# Holder_PCB_v1.net
KiCad netlist of a schematic drawn in Altium Designer
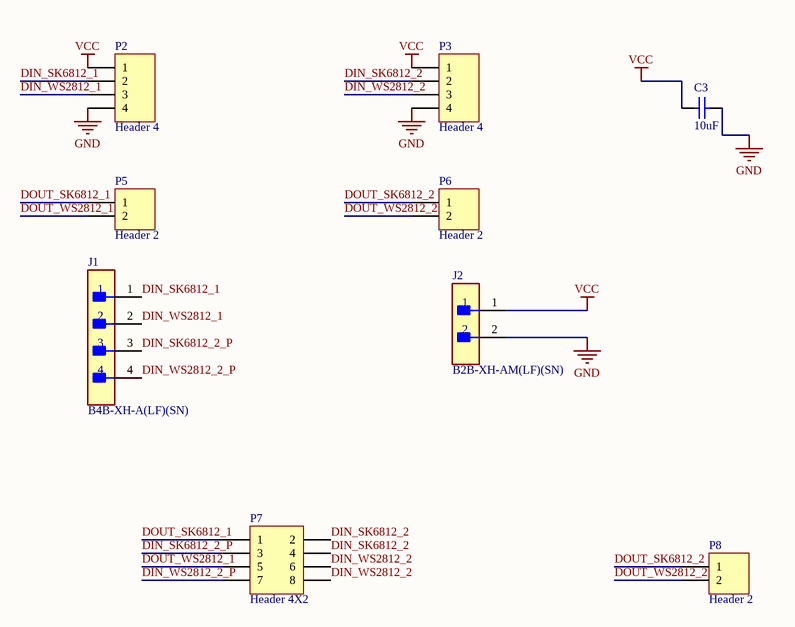
[diagram p0: Holder_PCB_v1.SchDoc]

(export (version "E")
  (design (tool "Eeschema 10.0.6"))
  (components
    (comp (ref "C3")
      (value "10uF")
      (footprint "0805C")
      (description "Capacitor")
      (fields (field (name "REVIEWED BY") "RM - 2018/08/05"))
      (libsource (lib "DSO") (part "C"))
    )
    (comp (ref "J1")
      (value "B4B-XH-A(LF)(SN)")
      (footprint "FP-B4B-XH-A_LF_SN-MFG")
      (description "CONN HEADER VERT 4POS 2.5MM")
      (libsource (lib "Altium Content Vault") (part "299a8cea1bdcbc3624fe62c390fa72c"))
    )
    (comp (ref "J2")
      (value "B2B-XH-AM(LF)(SN)")
      (footprint "FP-B2B-XH-AM_LF_SN-MFG")
      (description "CONN HEADER VERT 2POS 2.5MM")
      (libsource (lib "Altium Content Vault") (part "3bc925449376181038e59eaffc5286c"))
    )
    (comp (ref "P2")
      (value "Header 4")
      (footprint "HDR1X4")
      (description "Header, 4-Pin")
      (fields (field (name "PUBLISHER") "Altium Limited"))
      (libsource (lib "Miscellaneous Connectors") (part "Header 4"))
    )
    (comp (ref "P3")
      (value "Header 4")
      (footprint "HDR1X4")
      (description "Header, 4-Pin")
      (fields (field (name "PUBLISHER") "Altium Limited"))
      (libsource (lib "Miscellaneous Connectors") (part "Header 4"))
    )
    (comp (ref "P5")
      (value "Header 2")
      (footprint "HDR1X2")
      (description "Header, 2-Pin")
      (fields (field (name "PUBLISHER") "Altium Limited"))
      (libsource (lib "Miscellaneous Connectors") (part "Header 2"))
    )
    (comp (ref "P6")
      (value "Header 2")
      (footprint "HDR1X2")
      (description "Header, 2-Pin")
      (fields (field (name "PUBLISHER") "Altium Limited"))
      (libsource (lib "Miscellaneous Connectors") (part "Header 2"))
    )
    (comp (ref "P7")
      (value "Header 4X2")
      (footprint "HDR2X4")
      (description "Header, 4-Pin, Dual row")
      (fields (field (name "PUBLISHER") "Altium Limited"))
      (libsource (lib "Miscellaneous Connectors") (part "Header 4X2"))
    )
    (comp (ref "P8")
      (value "Header 2")
      (footprint "HDR1X2")
      (description "Header, 2-Pin")
      (fields (field (name "PUBLISHER") "Altium Limited"))
      (libsource (lib "Miscellaneous Connectors") (part "Header 2"))
    )
  )
  (nets
    (net (code "1") (name "/DIN_SK6812_1") (class "Default")
      (node (ref "J1") (pin "1") (pinfunction "1_1") (pintype "passive"))
      (node (ref "P2") (pin "2") (pinfunction "2_2") (pintype "passive"))
    )
    (net (code "2") (name "/DIN_SK6812_2") (class "Default")
      (node (ref "P3") (pin "2") (pinfunction "2_2") (pintype "passive"))
      (node (ref "P7") (pin "2") (pinfunction "2_2") (pintype "passive"))
      (node (ref "P7") (pin "4") (pinfunction "4_4") (pintype "passive"))
    )
    (net (code "3") (name "/DIN_SK6812_2_P") (class "Default")
      (node (ref "J1") (pin "3") (pinfunction "3_3") (pintype "passive"))
      (node (ref "P7") (pin "3") (pinfunction "3_3") (pintype "passive"))
    )
    (net (code "4") (name "/DIN_WS2812_1") (class "Default")
      (node (ref "J1") (pin "2") (pinfunction "2_2") (pintype "passive"))
      (node (ref "P2") (pin "3") (pinfunction "3_3") (pintype "passive"))
    )
    (net (code "5") (name "/DIN_WS2812_2") (class "Default")
      (node (ref "P3") (pin "3") (pinfunction "3_3") (pintype "passive"))
      (node (ref "P7") (pin "6") (pinfunction "6_6") (pintype "passive"))
      (node (ref "P7") (pin "8") (pinfunction "8_8") (pintype "passive"))
    )
    (net (code "6") (name "/DIN_WS2812_2_P") (class "Default")
      (node (ref "J1") (pin "4") (pinfunction "4_4") (pintype "passive"))
      (node (ref "P7") (pin "7") (pinfunction "7_7") (pintype "passive"))
    )
    (net (code "7") (name "/DOUT_SK6812_1") (class "Default")
      (node (ref "P5") (pin "1") (pinfunction "1_1") (pintype "passive"))
      (node (ref "P7") (pin "1") (pinfunction "1_1") (pintype "passive"))
    )
    (net (code "8") (name "/DOUT_SK6812_2") (class "Default")
      (node (ref "P6") (pin "1") (pinfunction "1_1") (pintype "passive"))
      (node (ref "P8") (pin "1") (pinfunction "1_1") (pintype "passive"))
    )
    (net (code "9") (name "/DOUT_WS2812_1") (class "Default")
      (node (ref "P5") (pin "2") (pinfunction "2_2") (pintype "passive"))
      (node (ref "P7") (pin "5") (pinfunction "5_5") (pintype "passive"))
    )
    (net (code "10") (name "/DOUT_WS2812_2") (class "Default")
      (node (ref "P6") (pin "2") (pinfunction "2_2") (pintype "passive"))
      (node (ref "P8") (pin "2") (pinfunction "2_2") (pintype "passive"))
    )
    (net (code "11") (name "GND") (class "Default")
      (node (ref "C3") (pin "1") (pinfunction "1_1") (pintype "passive"))
      (node (ref "J2") (pin "2") (pinfunction "2_2") (pintype "passive"))
      (node (ref "P2") (pin "4") (pinfunction "4_4") (pintype "passive"))
      (node (ref "P3") (pin "4") (pinfunction "4_4") (pintype "passive"))
    )
    (net (code "12") (name "VCC") (class "Default")
      (node (ref "C3") (pin "2") (pinfunction "2_2") (pintype "passive"))
      (node (ref "J2") (pin "1") (pinfunction "1_1") (pintype "passive"))
      (node (ref "P2") (pin "1") (pinfunction "1_1") (pintype "passive"))
      (node (ref "P3") (pin "1") (pinfunction "1_1") (pintype "passive"))
    )
  )
)
